# eNode_Spark.net
KiCad netlist of a schematic drawn in EAGLE
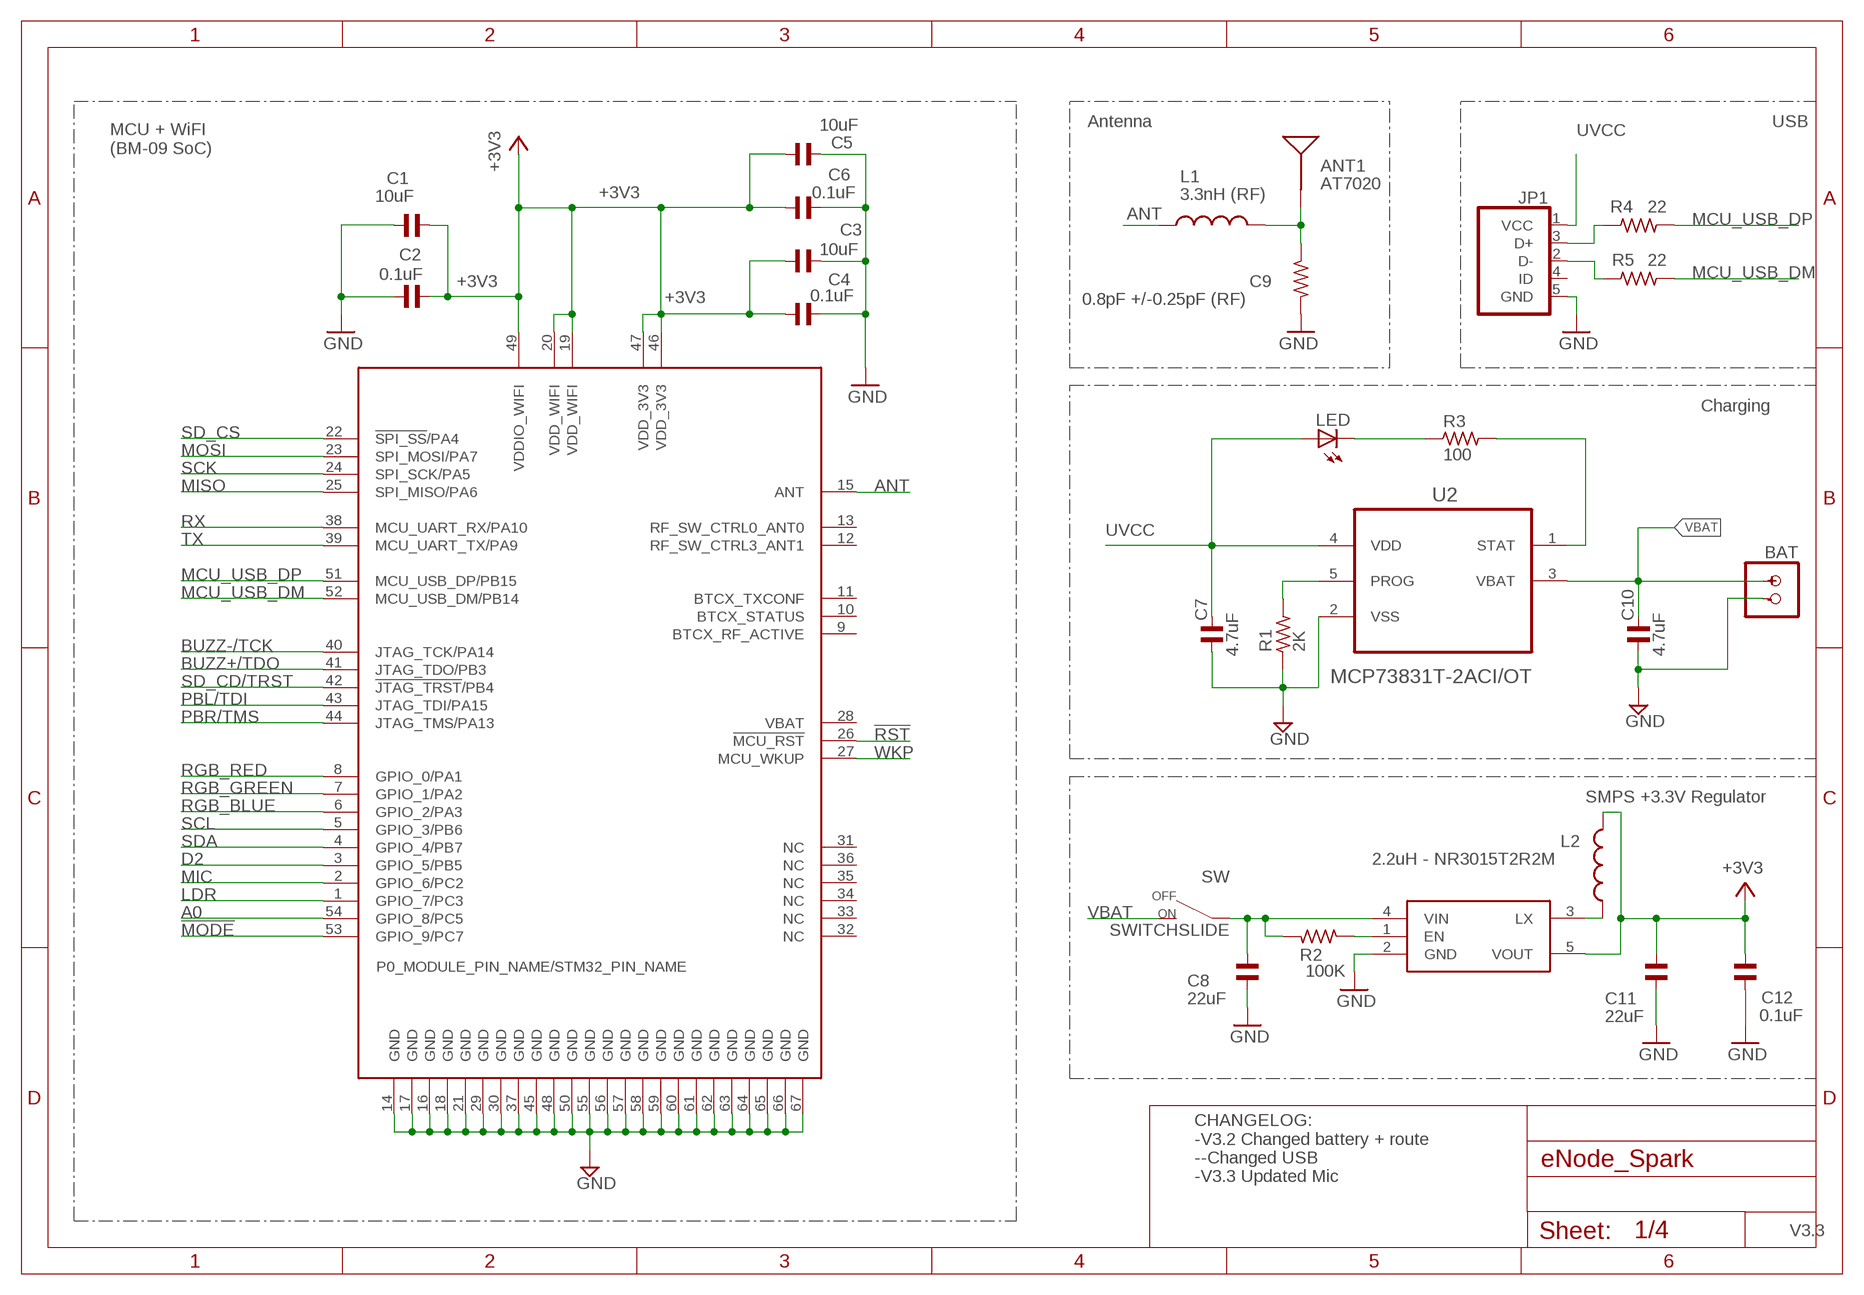
[diagram p0: schematic, sheet 1]
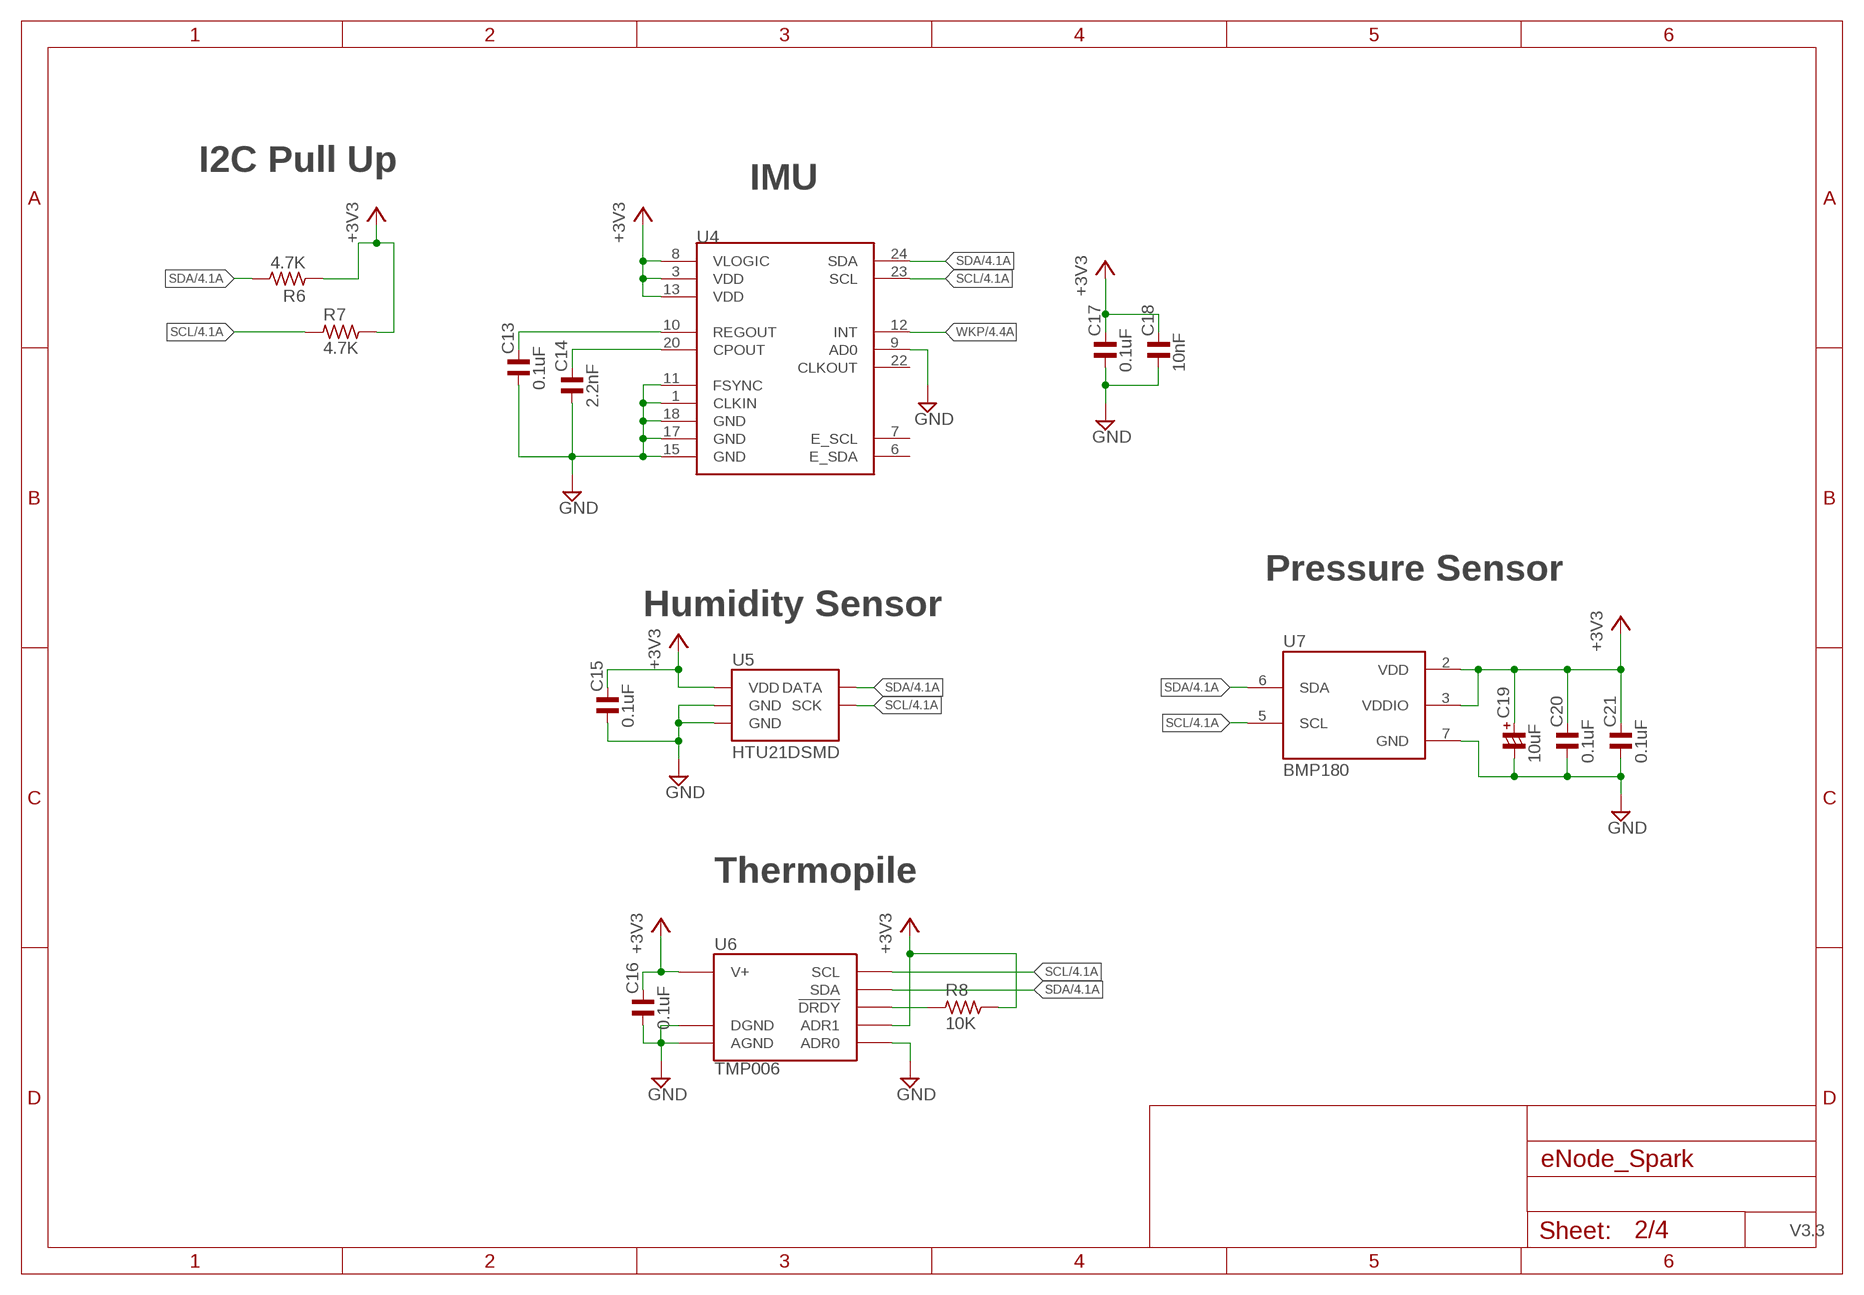
[diagram p1: schematic, sheet 2]
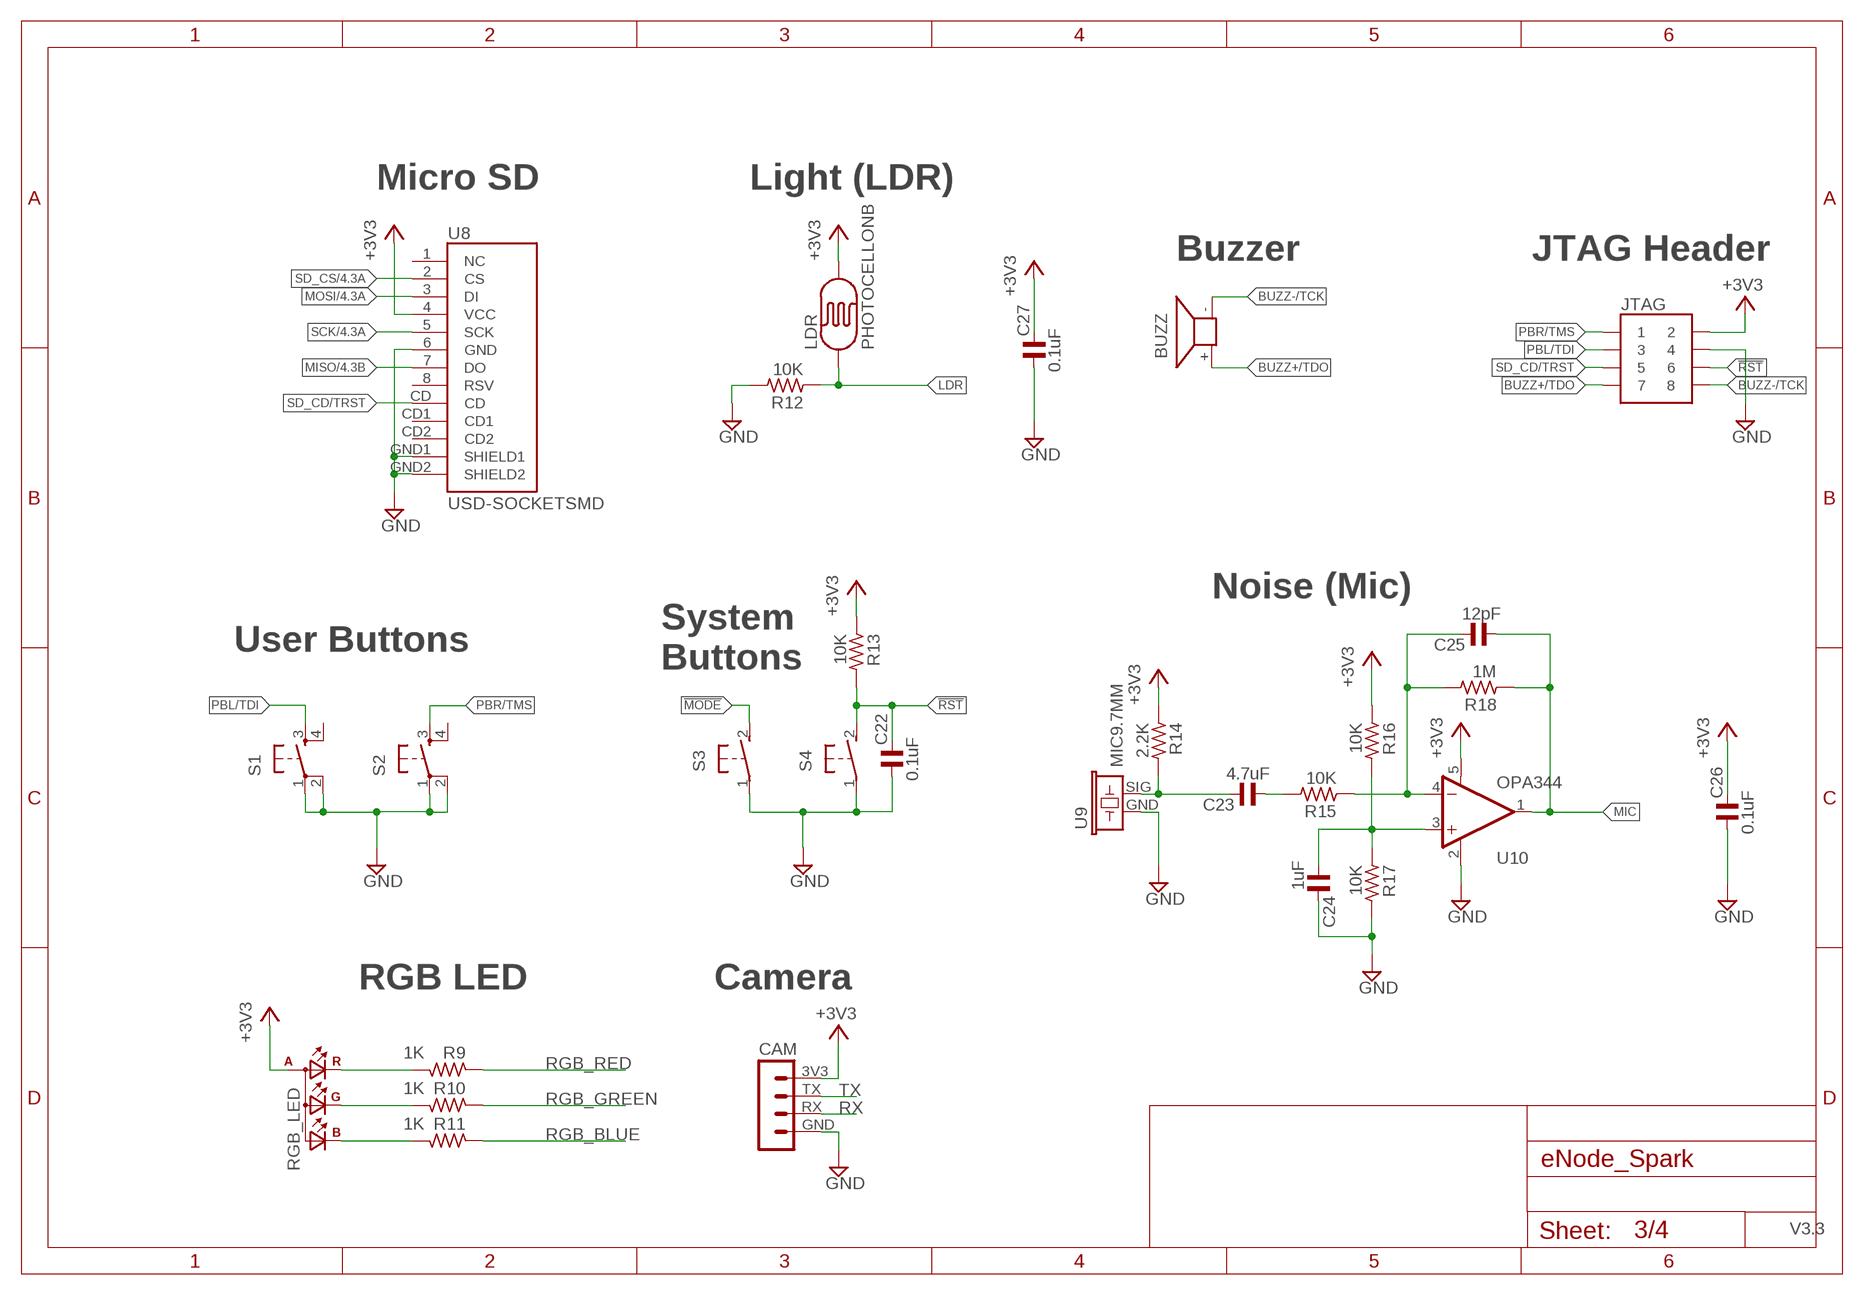
[diagram p2: schematic, sheet 3]
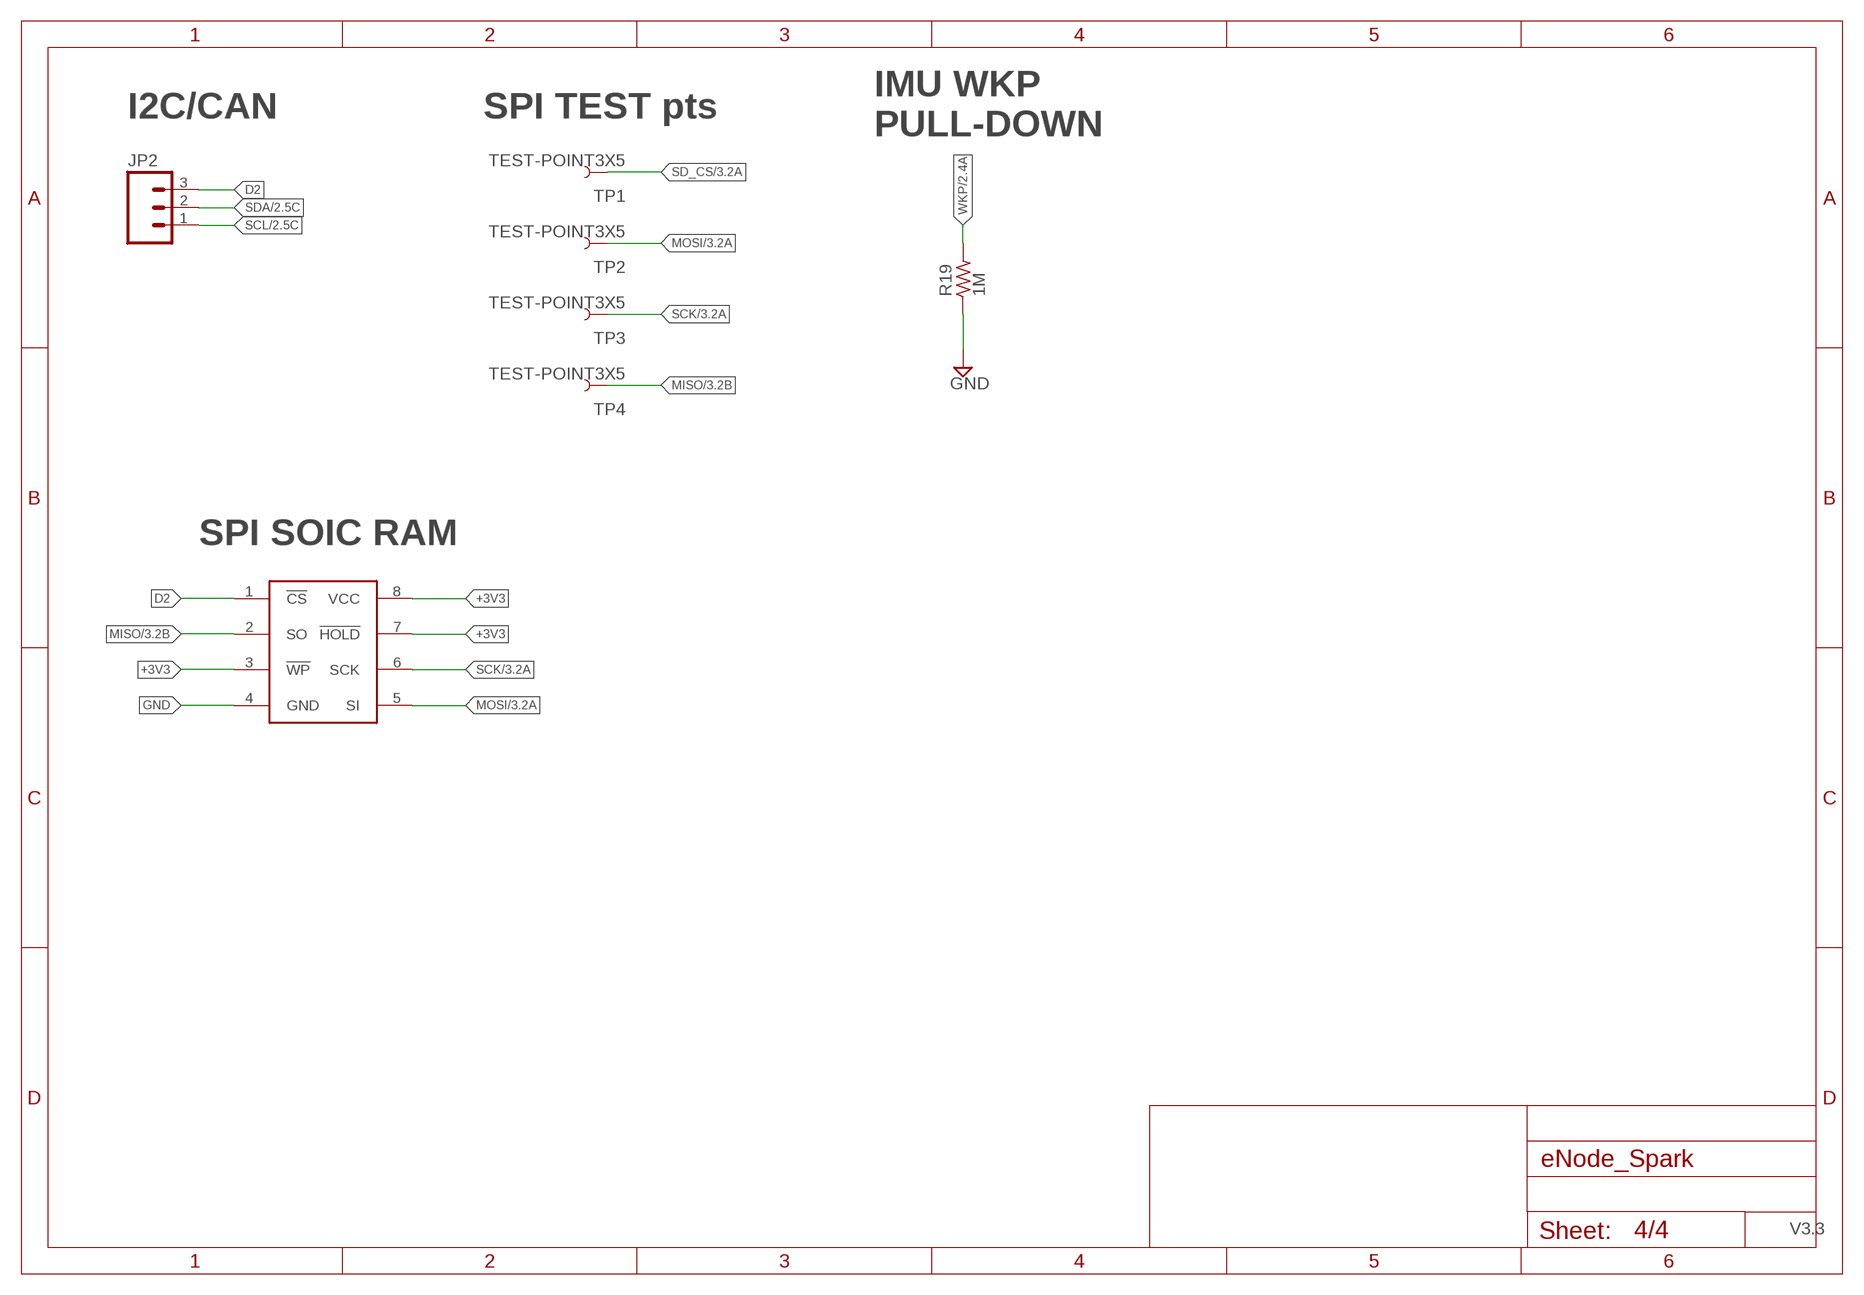
[diagram p3: schematic, sheet 4]

(export (version "E")
  (design (tool "Eeschema 10.0.6"))
  (components
    (comp (ref "JP2")
      (value "M03PTH")
      (footprint "eagle-import:1X03")
      (libsource (lib "eagle-import") (part "M03PTH"))
    )
    (comp (ref "R19")
      (value "1M")
      (footprint "eagle-import:R0402")
      (libsource (lib "eagle-import") (part "R_0402"))
    )
    (comp (ref "TP1")
      (value "TEST-POINT3X5")
      (footprint "eagle-import:PAD.03X.05")
      (libsource (lib "eagle-import") (part "TEST-POINT3X5"))
    )
    (comp (ref "TP2")
      (value "TEST-POINT3X5")
      (footprint "eagle-import:PAD.03X.05")
      (libsource (lib "eagle-import") (part "TEST-POINT3X5"))
    )
    (comp (ref "TP3")
      (value "TEST-POINT3X5")
      (footprint "eagle-import:PAD.03X.05")
      (libsource (lib "eagle-import") (part "TEST-POINT3X5"))
    )
    (comp (ref "TP4")
      (value "TEST-POINT3X5")
      (footprint "eagle-import:PAD.03X.05")
      (libsource (lib "eagle-import") (part "TEST-POINT3X5"))
    )
    (comp (ref "U11")
      (value "FRAM")
      (footprint "eagle-import:SO08")
      (libsource (lib "eagle-import") (part "FRAM"))
    )
    (comp (ref "C13")
      (value "0.1uF")
      (footprint "eagle-import:C0402")
      (libsource (lib "eagle-import") (part "C_0402"))
    )
    (comp (ref "C14")
      (value "2.2nF")
      (footprint "eagle-import:C0402")
      (libsource (lib "eagle-import") (part "C_0402"))
    )
    (comp (ref "C15")
      (value "0.1uF")
      (footprint "eagle-import:C0402")
      (libsource (lib "eagle-import") (part "C_0402"))
    )
    (comp (ref "C16")
      (value "0.1uF")
      (footprint "eagle-import:C0402")
      (libsource (lib "eagle-import") (part "C_0402"))
    )
    (comp (ref "C17")
      (value "0.1uF")
      (footprint "eagle-import:C0402")
      (libsource (lib "eagle-import") (part "C_0402"))
    )
    (comp (ref "C18")
      (value "10nF")
      (footprint "eagle-import:C0402")
      (libsource (lib "eagle-import") (part "C_0402"))
    )
    (comp (ref "C19")
      (value "10uF")
      (footprint "eagle-import:C1206_T")
      (libsource (lib "eagle-import") (part "CP_1206/T"))
    )
    (comp (ref "C20")
      (value "0.1uF")
      (footprint "eagle-import:C0402")
      (libsource (lib "eagle-import") (part "C_0402"))
    )
    (comp (ref "C21")
      (value "0.1uF")
      (footprint "eagle-import:C0402")
      (libsource (lib "eagle-import") (part "C_0402"))
    )
    (comp (ref "R6")
      (value "4.7K")
      (footprint "eagle-import:R0402")
      (libsource (lib "eagle-import") (part "R_0402"))
    )
    (comp (ref "R7")
      (value "4.7K")
      (footprint "eagle-import:R0402")
      (libsource (lib "eagle-import") (part "R_0402"))
    )
    (comp (ref "R8")
      (value "10K")
      (footprint "eagle-import:R0603")
      (libsource (lib "eagle-import") (part "R_0603"))
    )
    (comp (ref "U4")
      (value "MPU-9150QFN-24-NP")
      (footprint "eagle-import:QFN-24-NP")
      (libsource (lib "eagle-import") (part "MPU-9150QFN-24-NP"))
    )
    (comp (ref "U5")
      (value "HTU21DSMD")
      (footprint "eagle-import:HTU21D")
      (libsource (lib "eagle-import") (part "HTU21DSMD"))
    )
    (comp (ref "U6")
      (value "TMP006")
      (footprint "eagle-import:BGA8DS")
      (libsource (lib "eagle-import") (part "TMP006"))
    )
    (comp (ref "U7")
      (value "BMP180")
      (footprint "eagle-import:BMP180")
      (libsource (lib "eagle-import") (part "BMP180"))
    )
    (comp (ref "ANT1")
      (value "AT7020")
      (footprint "eagle-import:AT7020")
      (libsource (lib "eagle-import") (part "AT7020"))
    )
    (comp (ref "BAT")
      (value "BATTERYSMT")
      (footprint "eagle-import:JST-2-SMD")
      (libsource (lib "eagle-import") (part "BATTERYSMT"))
    )
    (comp (ref "C1")
      (value "10uF")
      (footprint "eagle-import:C0402")
      (libsource (lib "eagle-import") (part "C_0402"))
    )
    (comp (ref "C2")
      (value "0.1uF")
      (footprint "eagle-import:C0402")
      (libsource (lib "eagle-import") (part "C_0402"))
    )
    (comp (ref "C3")
      (value "10uF")
      (footprint "eagle-import:C0402")
      (libsource (lib "eagle-import") (part "C_0402"))
    )
    (comp (ref "C4")
      (value "0.1uF")
      (footprint "eagle-import:C0402")
      (libsource (lib "eagle-import") (part "C_0402"))
    )
    (comp (ref "C5")
      (value "10uF")
      (footprint "eagle-import:C0402")
      (libsource (lib "eagle-import") (part "C_0402"))
    )
    (comp (ref "C6")
      (value "0.1uF")
      (footprint "eagle-import:C0402")
      (libsource (lib "eagle-import") (part "C_0402"))
    )
    (comp (ref "C7")
      (value "4.7uF")
      (footprint "eagle-import:C0402")
      (libsource (lib "eagle-import") (part "C_0402"))
    )
    (comp (ref "C8")
      (value "22uF")
      (footprint "eagle-import:C0603")
      (libsource (lib "eagle-import") (part "C_0603"))
    )
    (comp (ref "C9")
      (value "0.8pF +/-0.25pF (RF)")
      (footprint "eagle-import:R0402_B")
      (libsource (lib "eagle-import") (part "R-US_"))
    )
    (comp (ref "C10")
      (value "4.7uF")
      (footprint "eagle-import:C0402")
      (libsource (lib "eagle-import") (part "C_0402"))
    )
    (comp (ref "C11")
      (value "22uF")
      (footprint "eagle-import:C0603")
      (libsource (lib "eagle-import") (part "C_0603"))
    )
    (comp (ref "C12")
      (value "0.1uF")
      (footprint "eagle-import:C0402")
      (libsource (lib "eagle-import") (part "C_0402"))
    )
    (comp (ref "JP1")
      (value "USB-RECEPTABLE")
      (footprint "eagle-import:FCI-10103594-0001LF")
      (libsource (lib "eagle-import") (part "USB-RECEPTABLE"))
    )
    (comp (ref "L1")
      (value "3.3nH (RF)")
      (footprint "eagle-import:L0402_B")
      (libsource (lib "eagle-import") (part "INDUCTOR"))
    )
    (comp (ref "L2")
      (value "2.2uH - NR3015T2R2M")
      (footprint "eagle-import:INDUCTOR-NR3015")
      (libsource (lib "eagle-import") (part "INDUCTORB"))
    )
    (comp (ref "LED")
      (value "LED")
      (footprint "eagle-import:SMARTLED-TTW")
      (libsource (lib "eagle-import") (part "LED"))
    )
    (comp (ref "R1")
      (value "2K")
      (footprint "eagle-import:R0603")
      (libsource (lib "eagle-import") (part "R_0603"))
    )
    (comp (ref "R2")
      (value "100K")
      (footprint "eagle-import:R0402")
      (libsource (lib "eagle-import") (part "R_0402"))
    )
    (comp (ref "R3")
      (value "100")
      (footprint "eagle-import:R0603")
      (libsource (lib "eagle-import") (part "R_0603"))
    )
    (comp (ref "R4")
      (value "22")
      (footprint "eagle-import:R0402")
      (libsource (lib "eagle-import") (part "R_0402"))
    )
    (comp (ref "R5")
      (value "22")
      (footprint "eagle-import:R0402")
      (libsource (lib "eagle-import") (part "R_0402"))
    )
    (comp (ref "SW")
      (value "SWITCHSLIDE")
      (footprint "eagle-import:CHANGE_OVER_SLIDE")
      (libsource (lib "eagle-import") (part "SWITCHSLIDE"))
    )
    (comp (ref "U1")
      (value "WM-N-BM-09")
      (footprint "eagle-import:WM-N-BM-09")
      (libsource (lib "eagle-import") (part "WM-N-BM-09"))
    )
    (comp (ref "U2")
      (value "MCP73831T-2ACI/OT")
      (footprint "eagle-import:SOT95P280X145-5N")
      (libsource (lib "eagle-import") (part "MCP73831T-2ACI/OT"))
    )
    (comp (ref "U3")
      (value "R8008-33")
      (footprint "eagle-import:SOT23-5")
      (libsource (lib "eagle-import") (part "R8008-33"))
    )
    (comp (ref "BUZZ")
      (value "BUZZER")
      (footprint "eagle-import:OFFBOARD_NOSIGN")
      (libsource (lib "eagle-import") (part "BUZZER"))
    )
    (comp (ref "C22")
      (value "0.1uF")
      (footprint "eagle-import:C0402")
      (libsource (lib "eagle-import") (part "C_0402"))
    )
    (comp (ref "C23")
      (value "4.7uF")
      (footprint "eagle-import:C0402")
      (libsource (lib "eagle-import") (part "C_0402"))
    )
    (comp (ref "C24")
      (value "1uF")
      (footprint "eagle-import:C0402")
      (libsource (lib "eagle-import") (part "C_0402"))
    )
    (comp (ref "C25")
      (value "12pF")
      (footprint "eagle-import:C0402")
      (libsource (lib "eagle-import") (part "C_0402"))
    )
    (comp (ref "C26")
      (value "0.1uF")
      (footprint "eagle-import:C0402")
      (libsource (lib "eagle-import") (part "C_0402"))
    )
    (comp (ref "C27")
      (value "0.1uF")
      (footprint "eagle-import:C0402")
      (libsource (lib "eagle-import") (part "C_0402"))
    )
    (comp (ref "CAM")
      (value "MA04-1")
      (footprint "eagle-import:MA04-1")
      (libsource (lib "eagle-import") (part "MA04-1"))
    )
    (comp (ref "JTAG")
      (value "JTAG_CONNECTOR")
      (footprint "eagle-import:JTAG_DIP")
      (libsource (lib "eagle-import") (part "JTAG_CONNECTOR"))
    )
    (comp (ref "LDR")
      (value "PHOTOCELLONB")
      (footprint "eagle-import:ON_BOARD")
      (libsource (lib "eagle-import") (part "PHOTOCELLONB"))
    )
    (comp (ref "R9")
      (value "1K")
      (footprint "eagle-import:R0402")
      (libsource (lib "eagle-import") (part "R_0402"))
    )
    (comp (ref "R10")
      (value "1K")
      (footprint "eagle-import:R0402")
      (libsource (lib "eagle-import") (part "R_0402"))
    )
    (comp (ref "R11")
      (value "1K")
      (footprint "eagle-import:R0402")
      (libsource (lib "eagle-import") (part "R_0402"))
    )
    (comp (ref "R12")
      (value "10K")
      (footprint "eagle-import:R0603")
      (libsource (lib "eagle-import") (part "R_0603"))
    )
    (comp (ref "R13")
      (value "10K")
      (footprint "eagle-import:R0402")
      (libsource (lib "eagle-import") (part "R_0402"))
    )
    (comp (ref "R14")
      (value "2.2K")
      (footprint "eagle-import:R0402")
      (libsource (lib "eagle-import") (part "R_0402"))
    )
    (comp (ref "R15")
      (value "10K")
      (footprint "eagle-import:R0402")
      (libsource (lib "eagle-import") (part "R_0402"))
    )
    (comp (ref "R16")
      (value "10K")
      (footprint "eagle-import:R0402")
      (libsource (lib "eagle-import") (part "R_0402"))
    )
    (comp (ref "R17")
      (value "10K")
      (footprint "eagle-import:R0402")
      (libsource (lib "eagle-import") (part "R_0402"))
    )
    (comp (ref "R18")
      (value "1M")
      (footprint "eagle-import:R0402")
      (libsource (lib "eagle-import") (part "R_0402"))
    )
    (comp (ref "RGB_LED")
      (value "TOPLED-3PLCC")
      (footprint "eagle-import:P-LCC-4-3")
      (libsource (lib "eagle-import") (part "TOPLED-3PLCC"))
    )
    (comp (ref "S1")
      (value "TAC_SWITCH_4SMD")
      (footprint "eagle-import:TACTILE_SWITCH_SMD_LARGE_4")
      (libsource (lib "eagle-import") (part "TAC_SWITCH_4SMD"))
    )
    (comp (ref "S2")
      (value "TAC_SWITCH_4SMD")
      (footprint "eagle-import:TACTILE_SWITCH_SMD_LARGE_4")
      (libsource (lib "eagle-import") (part "TAC_SWITCH_4SMD"))
    )
    (comp (ref "S3")
      (value "MODE")
      (footprint "eagle-import:DTSM-3")
      (libsource (lib "eagle-import") (part "TAC_SWITCH_2MULTICOMP"))
    )
    (comp (ref "S4")
      (value "RESET")
      (footprint "eagle-import:DTSM-3")
      (libsource (lib "eagle-import") (part "TAC_SWITCH_2MULTICOMP"))
    )
    (comp (ref "U8")
      (value "USD-SOCKETSMD")
      (footprint "eagle-import:MICRO-SD-SOCKET-PP")
      (libsource (lib "eagle-import") (part "USD-SOCKETSMD"))
    )
    (comp (ref "U9")
      (value "MIC9.7MM")
      (footprint "eagle-import:MIC-9.7MM")
      (libsource (lib "eagle-import") (part "MIC9.7MM"))
    )
    (comp (ref "U10")
      (value "OPA344")
      (footprint "eagle-import:SOT23-5")
      (libsource (lib "eagle-import") (part "OPA344"))
    )
  )
  (nets
    (net (code "1") (name "+3V3") (class "Default")
      (node (ref "C1") (pin "2") (pinfunction "2_2") (pintype "passive"))
      (node (ref "C11") (pin "1") (pinfunction "1_1") (pintype "passive"))
      (node (ref "C12") (pin "1") (pinfunction "1_1") (pintype "passive"))
      (node (ref "C15") (pin "2") (pinfunction "2_2") (pintype "passive"))
      (node (ref "C16") (pin "2") (pinfunction "2_2") (pintype "passive"))
      (node (ref "C17") (pin "2") (pinfunction "2_2") (pintype "passive"))
      (node (ref "C18") (pin "2") (pinfunction "2_2") (pintype "passive"))
      (node (ref "C19") (pin "+") (pinfunction "+_+") (pintype "passive"))
      (node (ref "C2") (pin "2") (pinfunction "2_2") (pintype "passive"))
      (node (ref "C20") (pin "2") (pinfunction "2_2") (pintype "passive"))
      (node (ref "C21") (pin "2") (pinfunction "2_2") (pintype "passive"))
      (node (ref "C26") (pin "2") (pinfunction "2_2") (pintype "passive"))
      (node (ref "C27") (pin "2") (pinfunction "2_2") (pintype "passive"))
      (node (ref "C3") (pin "1") (pinfunction "1_1") (pintype "passive"))
      (node (ref "C4") (pin "2") (pinfunction "2_2") (pintype "passive"))
      (node (ref "C5") (pin "1") (pinfunction "1_1") (pintype "passive"))
      (node (ref "C6") (pin "2") (pinfunction "2_2") (pintype "passive"))
      (node (ref "CAM") (pin "3V3") (pinfunction "3V3_3V3") (pintype "passive"))
      (node (ref "JTAG") (pin "2") (pinfunction "2_2") (pintype "bidirectional"))
      (node (ref "L2") (pin "2") (pinfunction "2_2") (pintype "passive"))
      (node (ref "LDR") (pin "2") (pinfunction "P$2_2") (pintype "bidirectional"))
      (node (ref "R13") (pin "1") (pinfunction "1_1") (pintype "passive"))
      (node (ref "R14") (pin "1") (pinfunction "1_1") (pintype "passive"))
      (node (ref "R16") (pin "1") (pinfunction "1_1") (pintype "passive"))
      (node (ref "R6") (pin "1") (pinfunction "1_1") (pintype "passive"))
      (node (ref "R7") (pin "2") (pinfunction "2_2") (pintype "passive"))
      (node (ref "R8") (pin "2") (pinfunction "2_2") (pintype "passive"))
      (node (ref "RGB_LED") (pin "A") (pinfunction "A2_A") (pintype "passive"))
      (node (ref "U1") (pin "19") (pinfunction "VDD_WIFI_19") (pintype "bidirectional"))
      (node (ref "U1") (pin "20") (pinfunction "VDD_WIFI_20") (pintype "bidirectional"))
      (node (ref "U1") (pin "46") (pinfunction "VDD_3V3_46") (pintype "bidirectional"))
      (node (ref "U1") (pin "47") (pinfunction "VDD_3V3_47") (pintype "bidirectional"))
      (node (ref "U1") (pin "49") (pinfunction "VDDIO_WIFI_49") (pintype "bidirectional"))
      (node (ref "U10") (pin "5") (pinfunction "V+_5") (pintype "power_in"))
      (node (ref "U11") (pin "3") (pinfunction "~{WP}_3") (pintype "bidirectional"))
      (node (ref "U11") (pin "7") (pinfunction "~{HOLD}_7") (pintype "bidirectional"))
      (node (ref "U11") (pin "8") (pinfunction "VCC_8") (pintype "bidirectional"))
      (node (ref "U3") (pin "5") (pinfunction "VOUT_5") (pintype "bidirectional"))
      (node (ref "U4") (pin "13") (pinfunction "VDD_13") (pintype "bidirectional"))
      (node (ref "U4") (pin "3") (pinfunction "VDD_3") (pintype "bidirectional"))
      (node (ref "U4") (pin "8") (pinfunction "VLOGIC_8") (pintype "bidirectional"))
      (node (ref "U5") (pin "VDD") (pinfunction "VDD_VDD") (pintype "power_in"))
      (node (ref "U6") (pin "A3") (pinfunction "V+_A3") (pintype "bidirectional"))
      (node (ref "U6") (pin "B1") (pinfunction "ADR1_B1") (pintype "bidirectional"))
      (node (ref "U7") (pin "2") (pinfunction "VDD_2") (pintype "power_in"))
      (node (ref "U7") (pin "3") (pinfunction "VDDIO_3") (pintype "power_in"))
      (node (ref "U8") (pin "4") (pinfunction "VCC_4") (pintype "bidirectional"))
    )
    (net (code "2") (name "A0") (class "Default")
      (node (ref "U1") (pin "54") (pinfunction "GPIO_8/PC5_54") (pintype "bidirectional"))
    )
    (net (code "3") (name "ANT") (class "Default")
      (node (ref "L1") (pin "1") (pinfunction "1_1") (pintype "passive"))
      (node (ref "U1") (pin "15") (pinfunction "ANT_15") (pintype "bidirectional"))
    )
    (net (code "4") (name "BUZZ+{slash}TDO") (class "Default")
      (node (ref "BUZZ") (pin "+") (pinfunction "+_+") (pintype "passive"))
      (node (ref "JTAG") (pin "7") (pinfunction "7_7") (pintype "bidirectional"))
      (node (ref "U1") (pin "41") (pinfunction "JTAG_TDO/PB3_41") (pintype "bidirectional"))
    )
    (net (code "5") (name "BUZZ-{slash}TCK") (class "Default")
      (node (ref "BUZZ") (pin "-") (pinfunction "-_-") (pintype "passive"))
      (node (ref "JTAG") (pin "8") (pinfunction "8_8") (pintype "bidirectional"))
      (node (ref "U1") (pin "40") (pinfunction "JTAG_TCK/PA14_40") (pintype "bidirectional"))
    )
    (net (code "6") (name "D2") (class "Default")
      (node (ref "JP2") (pin "3") (pinfunction "3_3") (pintype "passive"))
      (node (ref "U1") (pin "3") (pinfunction "GPIO_5/PB5_3") (pintype "bidirectional"))
      (node (ref "U11") (pin "1") (pinfunction "~{CS}_1") (pintype "bidirectional"))
    )
    (net (code "7") (name "GND") (class "Default")
      (node (ref "BAT") (pin "-") (pinfunction "-_-") (pintype "passive"))
      (node (ref "C1") (pin "1") (pinfunction "1_1") (pintype "passive"))
      (node (ref "C10") (pin "1") (pinfunction "1_1") (pintype "passive"))
      (node (ref "C11") (pin "2") (pinfunction "2_2") (pintype "passive"))
      (node (ref "C12") (pin "2") (pinfunction "2_2") (pintype "passive"))
      (node (ref "C13") (pin "1") (pinfunction "1_1") (pintype "passive"))
      (node (ref "C14") (pin "1") (pinfunction "1_1") (pintype "passive"))
      (node (ref "C15") (pin "1") (pinfunction "1_1") (pintype "passive"))
      (node (ref "C16") (pin "1") (pinfunction "1_1") (pintype "passive"))
      (node (ref "C17") (pin "1") (pinfunction "1_1") (pintype "passive"))
      (node (ref "C18") (pin "1") (pinfunction "1_1") (pintype "passive"))
      (node (ref "C19") (pin "-") (pinfunction "-_-") (pintype "passive"))
      (node (ref "C2") (pin "1") (pinfunction "1_1") (pintype "passive"))
      (node (ref "C20") (pin "1") (pinfunction "1_1") (pintype "passive"))
      (node (ref "C21") (pin "1") (pinfunction "1_1") (pintype "passive"))
      (node (ref "C22") (pin "1") (pinfunction "1_1") (pintype "passive"))
      (node (ref "C24") (pin "2") (pinfunction "2_2") (pintype "passive"))
      (node (ref "C26") (pin "1") (pinfunction "1_1") (pintype "passive"))
      (node (ref "C27") (pin "1") (pinfunction "1_1") (pintype "passive"))
      (node (ref "C3") (pin "2") (pinfunction "2_2") (pintype "passive"))
      (node (ref "C4") (pin "1") (pinfunction "1_1") (pintype "passive"))
      (node (ref "C5") (pin "2") (pinfunction "2_2") (pintype "passive"))
      (node (ref "C6") (pin "1") (pinfunction "1_1") (pintype "passive"))
      (node (ref "C7") (pin "1") (pinfunction "1_1") (pintype "passive"))
      (node (ref "C8") (pin "2") (pinfunction "2_2") (pintype "passive"))
      (node (ref "C9") (pin "2") (pinfunction "2_2") (pintype "passive"))
      (node (ref "CAM") (pin "GND") (pinfunction "GND_GND") (pintype "passive"))
      (node (ref "JP1") (pin "5") (pinfunction "GND_5") (pintype "bidirectional"))
      (node (ref "JTAG") (pin "4") (pinfunction "4_4") (pintype "bidirectional"))
      (node (ref "R1") (pin "1") (pinfunction "1_1") (pintype "passive"))
      (node (ref "R12") (pin "2") (pinfunction "2_2") (pintype "passive"))
      (node (ref "R17") (pin "2") (pinfunction "2_2") (pintype "passive"))
      (node (ref "R19") (pin "1") (pinfunction "1_1") (pintype "passive"))
      (node (ref "S1") (pin "1") (pinfunction "1_1") (pintype "passive"))
      (node (ref "S1") (pin "2") (pinfunction "2_2") (pintype "passive"))
      (node (ref "S2") (pin "1") (pinfunction "1_1") (pintype "passive"))
      (node (ref "S2") (pin "2") (pinfunction "2_2") (pintype "passive"))
      (node (ref "S3") (pin "1") (pinfunction "1_1") (pintype "passive"))
      (node (ref "S4") (pin "1") (pinfunction "1_1") (pintype "passive"))
      (node (ref "U1") (pin "14") (pinfunction "GND_14") (pintype "bidirectional"))
      (node (ref "U1") (pin "16") (pinfunction "GND_16") (pintype "bidirectional"))
      (node (ref "U1") (pin "17") (pinfunction "GND_17") (pintype "bidirectional"))
      (node (ref "U1") (pin "18") (pinfunction "GND_18") (pintype "bidirectional"))
      (node (ref "U1") (pin "21") (pinfunction "GND_21") (pintype "bidirectional"))
      (node (ref "U1") (pin "29") (pinfunction "GND_29") (pintype "bidirectional"))
      (node (ref "U1") (pin "30") (pinfunction "GND_30") (pintype "bidirectional"))
      (node (ref "U1") (pin "37") (pinfunction "GND_37") (pintype "bidirectional"))
      (node (ref "U1") (pin "45") (pinfunction "GND_45") (pintype "bidirectional"))
      (node (ref "U1") (pin "48") (pinfunction "GND_48") (pintype "bidirectional"))
      (node (ref "U1") (pin "50") (pinfunction "GND_50") (pintype "bidirectional"))
      (node (ref "U1") (pin "55") (pinfunction "GND_55") (pintype "bidirectional"))
      (node (ref "U1") (pin "56") (pinfunction "GND_56") (pintype "bidirectional"))
      (node (ref "U1") (pin "57") (pinfunction "GND_57") (pintype "bidirectional"))
      (node (ref "U1") (pin "58") (pinfunction "GND_58") (pintype "bidirectional"))
      (node (ref "U1") (pin "59") (pinfunction "GND_59") (pintype "bidirectional"))
      (node (ref "U1") (pin "60") (pinfunction "GND_60") (pintype "bidirectional"))
      (node (ref "U1") (pin "61") (pinfunction "GND_61") (pintype "bidirectional"))
      (node (ref "U1") (pin "62") (pinfunction "GND_62") (pintype "bidirectional"))
      (node (ref "U1") (pin "63") (pinfunction "GND_63") (pintype "bidirectional"))
      (node (ref "U1") (pin "64") (pinfunction "GND_64") (pintype "bidirectional"))
      (node (ref "U1") (pin "65") (pinfunction "GND_65") (pintype "bidirectional"))
      (node (ref "U1") (pin "66") (pinfunction "GND_66") (pintype "bidirectional"))
      (node (ref "U1") (pin "67") (pinfunction "GND_67") (pintype "bidirectional"))
      (node (ref "U10") (pin "2") (pinfunction "V-_2") (pintype "power_in"))
      (node (ref "U11") (pin "4") (pinfunction "GND_4") (pintype "bidirectional"))
      (node (ref "U2") (pin "2") (pinfunction "VSS_2") (pintype "power_in"))
      (node (ref "U3") (pin "2") (pinfunction "GND_2") (pintype "bidirectional"))
      (node (ref "U4") (pin "1") (pinfunction "CLKIN_1") (pintype "bidirectional"))
      (node (ref "U4") (pin "11") (pinfunction "FSYNC_11") (pintype "bidirectional"))
      (node (ref "U4") (pin "15") (pinfunction "GND_15") (pintype "bidirectional"))
      (node (ref "U4") (pin "17") (pinfunction "GND_17") (pintype "bidirectional"))
      (node (ref "U4") (pin "18") (pinfunction "GND_18") (pintype "bidirectional"))
      (node (ref "U4") (pin "9") (pinfunction "AD0_9") (pintype "bidirectional"))
      (node (ref "U5") (pin "7") (pinfunction "GND_7") (pintype "power_in"))
      (node (ref "U5") (pin "GND") (pinfunction "GND_GND") (pintype "power_in"))
      (node (ref "U6") (pin "A1") (pinfunction "DGND_A1") (pintype "bidirectional"))
      (node (ref "U6") (pin "A2") (pinfunction "AGND_A2") (pintype "bidirectional"))
      (node (ref "U6") (pin "C1") (pinfunction "ADR0_C1") (pintype "bidirectional"))
      (node (ref "U7") (pin "7") (pinfunction "GND_7") (pintype "power_in"))
      (node (ref "U8") (pin "6") (pinfunction "GND_6") (pintype "bidirectional"))
      (node (ref "U8") (pin "GND1") (pinfunction "SHIELD1_GND1") (pintype "bidirectional"))
      (node (ref "U8") (pin "GND2") (pinfunction "SHIELD2_GND2") (pintype "bidirectional"))
      (node (ref "U9") (pin "GND") (pinfunction "GND_GND") (pintype "passive"))
    )
    (net (code "8") (name "LDR") (class "Default")
      (node (ref "LDR") (pin "1") (pinfunction "P$1_1") (pintype "bidirectional"))
      (node (ref "R12") (pin "1") (pinfunction "1_1") (pintype "passive"))
      (node (ref "U1") (pin "1") (pinfunction "GPIO_7/PC3_1") (pintype "bidirectional"))
    )
    (net (code "9") (name "MCU_USB_DM") (class "Default")
      (node (ref "R5") (pin "1") (pinfunction "1_1") (pintype "passive"))
      (node (ref "U1") (pin "52") (pinfunction "MCU_USB_DM/PB14_52") (pintype "bidirectional"))
    )
    (net (code "10") (name "MCU_USB_DP") (class "Default")
      (node (ref "R4") (pin "1") (pinfunction "1_1") (pintype "passive"))
      (node (ref "U1") (pin "51") (pinfunction "MCU_USB_DP/PB15_51") (pintype "bidirectional"))
    )
    (net (code "11") (name "MIC") (class "Default")
      (node (ref "C25") (pin "1") (pinfunction "1_1") (pintype "passive"))
      (node (ref "R18") (pin "1") (pinfunction "1_1") (pintype "passive"))
      (node (ref "U1") (pin "2") (pinfunction "GPIO_6/PC2_2") (pintype "bidirectional"))
      (node (ref "U10") (pin "1") (pinfunction "OUT_1") (pintype "output"))
    )
    (net (code "12") (name "MISO") (class "Default")
      (node (ref "TP4") (pin "P$1") (pinfunction "1_P$1") (pintype "bidirectional"))
      (node (ref "U1") (pin "25") (pinfunction "SPI_MISO/PA6_25") (pintype "bidirectional"))
      (node (ref "U11") (pin "2") (pinfunction "SO_2") (pintype "bidirectional"))
      (node (ref "U8") (pin "7") (pinfunction "DO_7") (pintype "bidirectional"))
    )
    (net (code "13") (name "MOSI") (class "Default")
      (node (ref "TP2") (pin "P$1") (pinfunction "1_P$1") (pintype "bidirectional"))
      (node (ref "U1") (pin "23") (pinfunction "SPI_MOSI/PA7_23") (pintype "bidirectional"))
      (node (ref "U11") (pin "5") (pinfunction "SI_5") (pintype "bidirectional"))
      (node (ref "U8") (pin "3") (pinfunction "DI_3") (pintype "bidirectional"))
    )
    (net (code "14") (name "Net-(ANT1-SIGNAL)") (class "Default")
      (node (ref "ANT1") (pin "1") (pinfunction "SIGNAL_1") (pintype "bidirectional"))
      (node (ref "C9") (pin "1") (pinfunction "1_1") (pintype "passive"))
      (node (ref "L1") (pin "2") (pinfunction "2_2") (pintype "passive"))
    )
    (net (code "15") (name "Net-(C23-Pad1)") (class "Default")
      (node (ref "C23") (pin "1") (pinfunction "1_1") (pintype "passive"))
      (node (ref "R15") (pin "2") (pinfunction "2_2") (pintype "passive"))
    )
    (net (code "16") (name "Net-(C23-Pad2)") (class "Default")
      (node (ref "C23") (pin "2") (pinfunction "2_2") (pintype "passive"))
      (node (ref "R14") (pin "2") (pinfunction "2_2") (pintype "passive"))
      (node (ref "U9") (pin "SIG") (pinfunction "SIG_SIG") (pintype "passive"))
    )
    (net (code "17") (name "Net-(JP1-D+)") (class "Default")
      (node (ref "JP1") (pin "3") (pinfunction "D+_3") (pintype "bidirectional"))
      (node (ref "R4") (pin "2") (pinfunction "2_2") (pintype "passive"))
    )
    (net (code "18") (name "Net-(JP1-D-)") (class "Default")
      (node (ref "JP1") (pin "2") (pinfunction "D-_2") (pintype "bidirectional"))
      (node (ref "R5") (pin "2") (pinfunction "2_2") (pintype "passive"))
    )
    (net (code "19") (name "Net-(LED-C)") (class "Default")
      (node (ref "LED") (pin "C@1") (pinfunction "C_C@1") (pintype "passive"))
      (node (ref "R3") (pin "1") (pinfunction "1_1") (pintype "passive"))
    )
    (net (code "20") (name "Net-(RGB_LED-CBLUE)") (class "Default")
      (node (ref "R11") (pin "1") (pinfunction "1_1") (pintype "passive"))
      (node (ref "RGB_LED") (pin "B") (pinfunction "CBLUE_B") (pintype "passive"))
    )
    (net (code "21") (name "Net-(RGB_LED-CGREEN)") (class "Default")
      (node (ref "R10") (pin "1") (pinfunction "1_1") (pintype "passive"))
      (node (ref "RGB_LED") (pin "G") (pinfunction "CGREEN_G") (pintype "passive"))
    )
    (net (code "22") (name "Net-(RGB_LED-CRED)") (class "Default")
      (node (ref "R9") (pin "1") (pinfunction "1_1") (pintype "passive"))
      (node (ref "RGB_LED") (pin "R") (pinfunction "CRED_R") (pintype "passive"))
    )
    (net (code "23") (name "Net-(U2-PROG)") (class "Default")
      (node (ref "R1") (pin "2") (pinfunction "2_2") (pintype "passive"))
      (node (ref "U2") (pin "5") (pinfunction "PROG_5") (pintype "input"))
    )
    (net (code "24") (name "Net-(U2-STAT)") (class "Default")
      (node (ref "R3") (pin "2") (pinfunction "2_2") (pintype "passive"))
      (node (ref "U2") (pin "1") (pinfunction "STAT_1") (pintype "output"))
    )
    (net (code "25") (name "Net-(U3-EN)") (class "Default")
      (node (ref "R2") (pin "1") (pinfunction "1_1") (pintype "passive"))
      (node (ref "U3") (pin "1") (pinfunction "EN_1") (pintype "bidirectional"))
    )
    (net (code "26") (name "Net-(U3-LX)") (class "Default")
      (node (ref "L2") (pin "1") (pinfunction "1_1") (pintype "passive"))
      (node (ref "U3") (pin "3") (pinfunction "LX_3") (pintype "bidirectional"))
    )
    (net (code "27") (name "Net-(U3-VIN)") (class "Default")
      (node (ref "C8") (pin "1") (pinfunction "1_1") (pintype "passive"))
      (node (ref "R2") (pin "2") (pinfunction "2_2") (pintype "passive"))
      (node (ref "SW") (pin "1") (pinfunction "1_1") (pintype "bidirectional"))
      (node (ref "U3") (pin "4") (pinfunction "VIN_4") (pintype "bidirectional"))
    )
    (net (code "28") (name "Net-(U4-CPOUT)") (class "Default")
      (node (ref "C14") (pin "2") (pinfunction "2_2") (pintype "passive"))
      (node (ref "U4") (pin "20") (pinfunction "CPOUT_20") (pintype "bidirectional"))
    )
    (net (code "29") (name "Net-(U4-REGOUT)") (class "Default")
      (node (ref "C13") (pin "2") (pinfunction "2_2") (pintype "passive"))
      (node (ref "U4") (pin "10") (pinfunction "REGOUT_10") (pintype "bidirectional"))
    )
    (net (code "30") (name "Net-(U6-~{DRDY})") (class "Default")
      (node (ref "R8") (pin "1") (pinfunction "1_1") (pintype "passive"))
      (node (ref "U6") (pin "C2") (pinfunction "~{DRDY}_C2") (pintype "bidirectional"))
    )
    (net (code "31") (name "Net-(U10-+IN)") (class "Default")
      (node (ref "C24") (pin "1") (pinfunction "1_1") (pintype "passive"))
      (node (ref "R16") (pin "2") (pinfunction "2_2") (pintype "passive"))
      (node (ref "R17") (pin "1") (pinfunction "1_1") (pintype "passive"))
      (node (ref "U10") (pin "3") (pinfunction "+IN_3") (pintype "input"))
    )
    (net (code "32") (name "Net-(U10--IN)") (class "Default")
      (node (ref "C25") (pin "2") (pinfunction "2_2") (pintype "passive"))
      (node (ref "R15") (pin "1") (pinfunction "1_1") (pintype "passive"))
      (node (ref "R18") (pin "2") (pinfunction "2_2") (pintype "passive"))
      (node (ref "U10") (pin "4") (pinfunction "-IN_4") (pintype "input"))
    )
    (net (code "33") (name "PBL{slash}TDI") (class "Default")
      (node (ref "JTAG") (pin "3") (pinfunction "3_3") (pintype "bidirectional"))
      (node (ref "S1") (pin "3") (pinfunction "3_3") (pintype "passive"))
      (node (ref "U1") (pin "43") (pinfunction "JTAG_TDI/PA15_43") (pintype "bidirectional"))
    )
    (net (code "34") (name "PBR{slash}TMS") (class "Default")
      (node (ref "JTAG") (pin "1") (pinfunction "1_1") (pintype "bidirectional"))
      (node (ref "S2") (pin "3") (pinfunction "3_3") (pintype "passive"))
      (node (ref "U1") (pin "44") (pinfunction "JTAG_TMS/PA13_44") (pintype "bidirectional"))
    )
    (net (code "35") (name "RGB_BLUE") (class "Default")
      (node (ref "R11") (pin "2") (pinfunction "2_2") (pintype "passive"))
      (node (ref "U1") (pin "6") (pinfunction "GPIO_2/PA3_6") (pintype "bidirectional"))
    )
    (net (code "36") (name "RGB_GREEN") (class "Default")
      (node (ref "R10") (pin "2") (pinfunction "2_2") (pintype "passive"))
      (node (ref "U1") (pin "7") (pinfunction "GPIO_1/PA2_7") (pintype "bidirectional"))
    )
    (net (code "37") (name "RGB_RED") (class "Default")
      (node (ref "R9") (pin "2") (pinfunction "2_2") (pintype "passive"))
      (node (ref "U1") (pin "8") (pinfunction "GPIO_0/PA1_8") (pintype "bidirectional"))
    )
    (net (code "38") (name "RX") (class "Default")
      (node (ref "CAM") (pin "RX") (pinfunction "RX_RX") (pintype "passive"))
      (node (ref "U1") (pin "38") (pinfunction "MCU_UART_RX/PA10_38") (pintype "bidirectional"))
    )
    (net (code "39") (name "SCK") (class "Default")
      (node (ref "TP3") (pin "P$1") (pinfunction "1_P$1") (pintype "bidirectional"))
      (node (ref "U1") (pin "24") (pinfunction "SPI_SCK/PA5_24") (pintype "bidirectional"))
      (node (ref "U11") (pin "6") (pinfunction "SCK_6") (pintype "bidirectional"))
      (node (ref "U8") (pin "5") (pinfunction "SCK_5") (pintype "bidirectional"))
    )
    (net (code "40") (name "SCL") (class "Default")
      (node (ref "JP2") (pin "1") (pinfunction "1_1") (pintype "passive"))
      (node (ref "R7") (pin "1") (pinfunction "1_1") (pintype "passive"))
      (node (ref "U1") (pin "5") (pinfunction "GPIO_3/PB6_5") (pintype "bidirectional"))
      (node (ref "U4") (pin "23") (pinfunction "SCL_23") (pintype "bidirectional"))
      (node (ref "U5") (pin "SCK") (pinfunction "SCK_SCK") (pintype "input"))
      (node (ref "U6") (pin "B3") (pinfunction "SCL_B3") (pintype "bidirectional"))
      (node (ref "U7") (pin "5") (pinfunction "SCL_5") (pintype "input"))
    )
    (net (code "41") (name "SDA") (class "Default")
      (node (ref "JP2") (pin "2") (pinfunction "2_2") (pintype "passive"))
      (node (ref "R6") (pin "2") (pinfunction "2_2") (pintype "passive"))
      (node (ref "U1") (pin "4") (pinfunction "GPIO_4/PB7_4") (pintype "bidirectional"))
      (node (ref "U4") (pin "24") (pinfunction "SDA_24") (pintype "bidirectional"))
      (node (ref "U5") (pin "DATA") (pinfunction "DATA_DATA") (pintype "bidirectional"))
      (node (ref "U6") (pin "C3") (pinfunction "SDA_C3") (pintype "bidirectional"))
      (node (ref "U7") (pin "6") (pinfunction "SDA_6") (pintype "bidirectional"))
    )
    (net (code "42") (name "SD_CD{slash}TRST") (class "Default")
      (node (ref "JTAG") (pin "5") (pinfunction "5_5") (pintype "bidirectional"))
      (node (ref "U1") (pin "42") (pinfunction "~{JTAG_TRST}/PB4_42") (pintype "bidirectional"))
      (node (ref "U8") (pin "CD") (pinfunction "CD_CD") (pintype "bidirectional"))
    )
    (net (code "43") (name "SD_CS") (class "Default")
      (node (ref "TP1") (pin "P$1") (pinfunction "1_P$1") (pintype "bidirectional"))
      (node (ref "U1") (pin "22") (pinfunction "~{SPI_SS}/PA4_22") (pintype "bidirectional"))
      (node (ref "U8") (pin "2") (pinfunction "CS_2") (pintype "bidirectional"))
    )
    (net (code "44") (name "TX") (class "Default")
      (node (ref "CAM") (pin "TX") (pinfunction "TX_TX") (pintype "passive"))
      (node (ref "U1") (pin "39") (pinfunction "MCU_UART_TX/PA9_39") (pintype "bidirectional"))
    )
    (net (code "45") (name "UVCC") (class "Default")
      (node (ref "C7") (pin "2") (pinfunction "2_2") (pintype "passive"))
      (node (ref "JP1") (pin "1") (pinfunction "VCC_1") (pintype "bidirectional"))
      (node (ref "LED") (pin "A@1") (pinfunction "A_A@1") (pintype "passive"))
      (node (ref "U2") (pin "4") (pinfunction "VDD_4") (pintype "power_in"))
    )
    (net (code "46") (name "VBAT") (class "Default")
      (node (ref "BAT") (pin "+") (pinfunction "+_+") (pintype "passive"))
      (node (ref "C10") (pin "2") (pinfunction "2_2") (pintype "passive"))
      (node (ref "SW") (pin "2") (pinfunction "2_2") (pintype "bidirectional"))
      (node (ref "U2") (pin "3") (pinfunction "VBAT_3") (pintype "output"))
    )
    (net (code "47") (name "WKP") (class "Default")
      (node (ref "R19") (pin "2") (pinfunction "2_2") (pintype "passive"))
      (node (ref "U1") (pin "27") (pinfunction "MCU_WKUP_27") (pintype "bidirectional"))
      (node (ref "U4") (pin "12") (pinfunction "INT_12") (pintype "bidirectional"))
    )
    (net (code "48") (name "unconnected-(JP1-ID-Pad4)") (class "Default")
      (node (ref "JP1") (pin "4") (pinfunction "ID_4") (pintype "bidirectional"))
    )
    (net (code "49") (name "unconnected-(S1-Pad4)") (class "Default")
      (node (ref "S1") (pin "4") (pinfunction "4_4") (pintype "passive"))
    )
    (net (code "50") (name "unconnected-(S2-Pad4)") (class "Default")
      (node (ref "S2") (pin "4") (pinfunction "4_4") (pintype "passive"))
    )
    (net (code "51") (name "unconnected-(U1-BTCX_RF_ACTIVE-Pad9)") (class "Default")
      (node (ref "U1") (pin "9") (pinfunction "BTCX_RF_ACTIVE_9") (pintype "bidirectional"))
    )
    (net (code "52") (name "unconnected-(U1-BTCX_STATUS-Pad10)") (class "Default")
      (node (ref "U1") (pin "10") (pinfunction "BTCX_STATUS_10") (pintype "bidirectional"))
    )
    (net (code "53") (name "unconnected-(U1-BTCX_TXCONF-Pad11)") (class "Default")
      (node (ref "U1") (pin "11") (pinfunction "BTCX_TXCONF_11") (pintype "bidirectional"))
    )
    (net (code "54") (name "unconnected-(U1-NC-Pad31)") (class "Default")
      (node (ref "U1") (pin "31") (pinfunction "NC_31") (pintype "bidirectional"))
    )
    (net (code "55") (name "unconnected-(U1-NC-Pad32)") (class "Default")
      (node (ref "U1") (pin "32") (pinfunction "NC_32") (pintype "bidirectional"))
    )
    (net (code "56") (name "unconnected-(U1-NC-Pad33)") (class "Default")
      (node (ref "U1") (pin "33") (pinfunction "NC_33") (pintype "bidirectional"))
    )
    (net (code "57") (name "unconnected-(U1-NC-Pad34)") (class "Default")
      (node (ref "U1") (pin "34") (pinfunction "NC_34") (pintype "bidirectional"))
    )
    (net (code "58") (name "unconnected-(U1-NC-Pad35)") (class "Default")
      (node (ref "U1") (pin "35") (pinfunction "NC_35") (pintype "bidirectional"))
    )
    (net (code "59") (name "unconnected-(U1-NC-Pad36)") (class "Default")
      (node (ref "U1") (pin "36") (pinfunction "NC_36") (pintype "bidirectional"))
    )
    (net (code "60") (name "unconnected-(U1-RF_SW_CTRL0_ANT0-Pad13)") (class "Default")
      (node (ref "U1") (pin "13") (pinfunction "RF_SW_CTRL0_ANT0_13") (pintype "bidirectional"))
    )
    (net (code "61") (name "unconnected-(U1-RF_SW_CTRL3_ANT1-Pad12)") (class "Default")
      (node (ref "U1") (pin "12") (pinfunction "RF_SW_CTRL3_ANT1_12") (pintype "bidirectional"))
    )
    (net (code "62") (name "unconnected-(U1-VBAT-Pad28)") (class "Default")
      (node (ref "U1") (pin "28") (pinfunction "VBAT_28") (pintype "bidirectional"))
    )
    (net (code "63") (name "unconnected-(U4-CLKOUT-Pad22)") (class "Default")
      (node (ref "U4") (pin "22") (pinfunction "CLKOUT_22") (pintype "bidirectional"))
    )
    (net (code "64") (name "unconnected-(U4-E_SCL-Pad7)") (class "Default")
      (node (ref "U4") (pin "7") (pinfunction "E_SCL_7") (pintype "bidirectional"))
    )
    (net (code "65") (name "unconnected-(U4-E_SDA-Pad6)") (class "Default")
      (node (ref "U4") (pin "6") (pinfunction "E_SDA_6") (pintype "bidirectional"))
    )
    (net (code "66") (name "unconnected-(U8-NC-Pad1)") (class "Default")
      (node (ref "U8") (pin "1") (pinfunction "NC_1") (pintype "bidirectional"))
    )
    (net (code "67") (name "unconnected-(U8-PadCD1)") (class "Default")
      (node (ref "U8") (pin "CD1") (pinfunction "CD1_CD1") (pintype "bidirectional"))
    )
    (net (code "68") (name "unconnected-(U8-PadCD2)") (class "Default")
      (node (ref "U8") (pin "CD2") (pinfunction "CD2_CD2") (pintype "bidirectional"))
    )
    (net (code "69") (name "unconnected-(U8-RSV-Pad8)") (class "Default")
      (node (ref "U8") (pin "8") (pinfunction "RSV_8") (pintype "bidirectional"))
    )
    (net (code "70") (name "~{MODE}") (class "Default")
      (node (ref "S3") (pin "2") (pinfunction "2_2") (pintype "passive"))
      (node (ref "U1") (pin "53") (pinfunction "GPIO_9/PC7_53") (pintype "bidirectional"))
    )
    (net (code "71") (name "~{RST}") (class "Default")
      (node (ref "C22") (pin "2") (pinfunction "2_2") (pintype "passive"))
      (node (ref "JTAG") (pin "6") (pinfunction "6_6") (pintype "bidirectional"))
      (node (ref "R13") (pin "2") (pinfunction "2_2") (pintype "passive"))
      (node (ref "S4") (pin "2") (pinfunction "2_2") (pintype "passive"))
      (node (ref "U1") (pin "26") (pinfunction "~{MCU_RST}_26") (pintype "bidirectional"))
    )
  )
)
